# Adafruit_TCS34725.net
KiCad netlist of a schematic drawn in Altium Designer
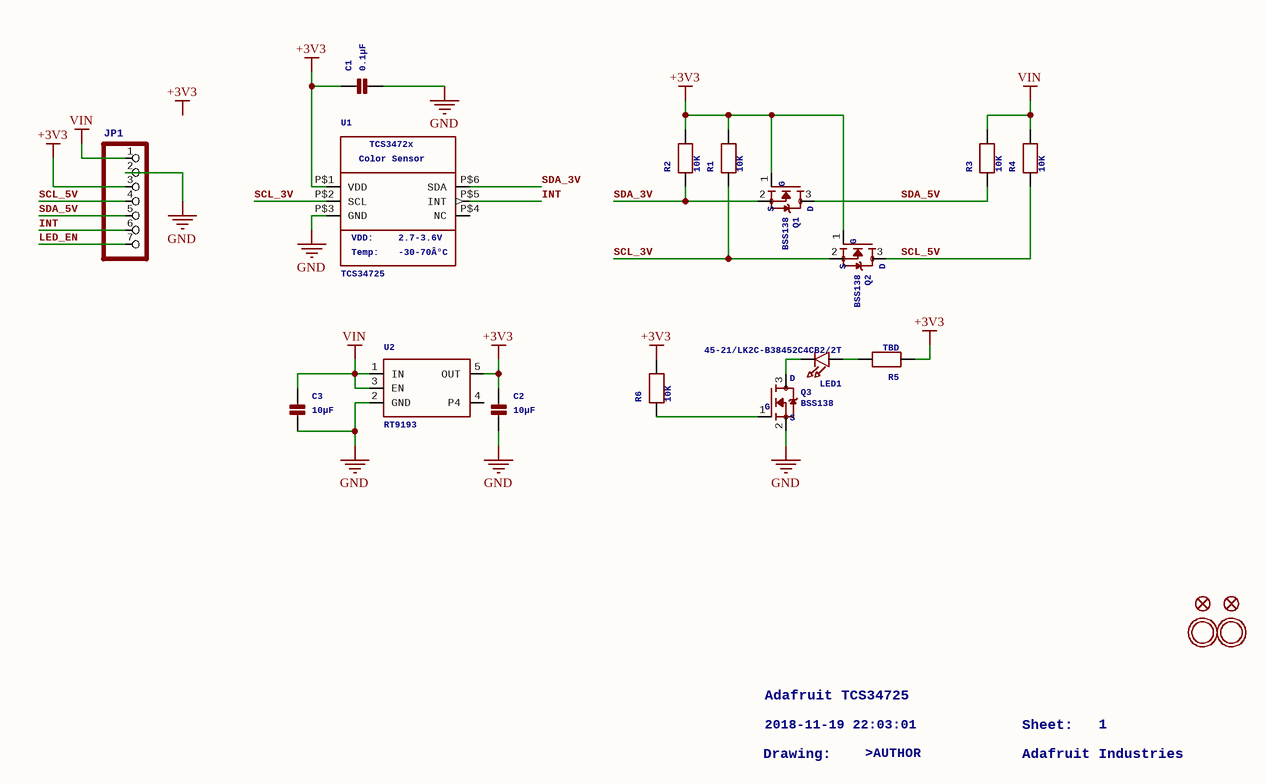
[diagram p0: Adafruit TCS34725.SchDoc]

(export (version "E")
  (design (tool "Eeschema 10.0.6"))
  (components
    (comp (ref "C1") (value "0.1µF") (footprint "_0805") (libsource (lib "") (part "CAP_CERAMIC_0805_1")))
    (comp (ref "C2")
      (value "10µF")
      (footprint "_0805")
      (libsource (lib "microbuilder") (part "CAP_CERAMIC_0805"))
    )
    (comp (ref "C3")
      (value "10µF")
      (footprint "_0805")
      (libsource (lib "microbuilder") (part "CAP_CERAMIC_0805"))
    )
    (comp (ref "FID1")
      (value "FIDUCIAL\"\"")
      (footprint "FIDUCIAL_1MM")
      (description "Fiducial Alignment PointsVarious fiducial points for machine vision alignment.")
      (libsource (lib "microbuilder") (part "FIDUCIAL{dblquote}{dblquote}"))
    )
    (comp (ref "FID2")
      (value "FIDUCIAL\"\"")
      (footprint "FIDUCIAL_1MM")
      (description "Fiducial Alignment PointsVarious fiducial points for machine vision alignment.")
      (libsource (lib "microbuilder") (part "FIDUCIAL{dblquote}{dblquote}"))
    )
    (comp (ref "JP1")
      (value "HEADER-1X770MIL")
      (footprint "1X07_ROUND_70")
      (description "PIN HEADER")
      (libsource (lib "microbuilder") (part "HEADER-1X770MIL"))
    )
    (comp (ref "LED1")
      (value "45-21/LK2C-B38452C4CB2/2T")
      (footprint "EVERLIGHT_45-21")
      (libsource (lib "microbuilder") (part "LEDEV45-21"))
    )
    (comp (ref "Q1")
      (value "BSS138")
      (footprint "SOT23-WIDE")
      (fields (field (name "D") "D") (field (name "S") "S") (field (name "G") "G"))
      (libsource (lib "microbuilder") (part "MOSFET-NWIDE"))
    )
    (comp (ref "Q2")
      (value "BSS138")
      (footprint "SOT23-WIDE")
      (fields (field (name "D") "D") (field (name "S") "S") (field (name "G") "G"))
      (libsource (lib "microbuilder") (part "MOSFET-NWIDE"))
    )
    (comp (ref "Q3")
      (value "BSS138")
      (footprint "SOT23-WIDE")
      (fields (field (name "D") "D") (field (name "S") "S") (field (name "G") "G"))
      (libsource (lib "microbuilder") (part "MOSFET-NWIDE"))
    )
    (comp (ref "R1")
      (value "10K")
      (footprint "_0805")
      (libsource (lib "microbuilder") (part "RESISTOR_0805"))
    )
    (comp (ref "R2")
      (value "10K")
      (footprint "_0805")
      (libsource (lib "microbuilder") (part "RESISTOR_0805"))
    )
    (comp (ref "R3")
      (value "10K")
      (footprint "_0805")
      (libsource (lib "microbuilder") (part "RESISTOR_0805"))
    )
    (comp (ref "R4")
      (value "10K")
      (footprint "_0805")
      (libsource (lib "microbuilder") (part "RESISTOR_0805"))
    )
    (comp (ref "R5")
      (value "TBD")
      (footprint "_0805")
      (libsource (lib "microbuilder") (part "RESISTOR_0805"))
    )
    (comp (ref "R6")
      (value "10K")
      (footprint "_0805")
      (libsource (lib "microbuilder") (part "RESISTOR_0805"))
    )
    (comp (ref "U$8")
      (value "MOUNTINGHOLE2.5")
      (footprint "MOUNTINGHOLE_2.5_PLATED")
      (description "Mounting HoleFor #2 screws (0.086\"/2.18mm width, 0.094\"/2.4mm hole) use 2.5mm")
      (libsource (lib "microbuilder") (part "MOUNTINGHOLE2.5"))
    )
    (comp (ref "U$14")
      (value "MOUNTINGHOLE2.5")
      (footprint "MOUNTINGHOLE_2.5_PLATED")
      (description "Mounting HoleFor #2 screws (0.086\"/2.18mm width, 0.094\"/2.4mm hole) use 2.5mm")
      (libsource (lib "microbuilder") (part "MOUNTINGHOLE2.5"))
    )
    (comp (ref "U1")
      (value "TCS34725")
      (footprint "TCS3472_FN6")
      (description "TCS3472 RGB + Clear Color SensorPart IDs")
      (fields
        (field (name "TCS3472X") "TCS3472x")
        (field (name "COLORSENSOR") "Color Sensor")
        (field (name "VDD") "VDD:")
        (field (name "TEMP") "Temp:")
        (field (name "2.7-3.6V") "2.7-3.6V")
        (field (name "-30-70掳C") "-30-70掳C")
      )
      (libsource (lib "microbuilder") (part "LIGHT_TCS3472"))
    )
    (comp (ref "U2")
      (value "RT9193")
      (footprint "SOT23-5")
      (libsource (lib "microbuilder") (part "VREG_SOT23-5"))
    )
  )
  (nets
    (net (code "1") (name "+3V3") (class "Default")
      (node (ref "C1") (pin "1") (pinfunction "P$1_1") (pintype "passive"))
      (node (ref "C2") (pin "1") (pinfunction "P$1_1") (pintype "passive"))
      (node (ref "JP1") (pin "3") (pinfunction "3_3") (pintype "passive"))
      (node (ref "Q1") (pin "1") (pinfunction "G_1") (pintype "passive"))
      (node (ref "Q2") (pin "1") (pinfunction "G_1") (pintype "passive"))
      (node (ref "R1") (pin "2") (pinfunction "2_2") (pintype "passive"))
      (node (ref "R2") (pin "2") (pinfunction "2_2") (pintype "passive"))
      (node (ref "R5") (pin "1") (pinfunction "1_1") (pintype "passive"))
      (node (ref "R6") (pin "2") (pinfunction "2_2") (pintype "passive"))
      (node (ref "U1") (pin "P$1") (pinfunction "VDD_P$1") (pintype "power_in"))
      (node (ref "U2") (pin "5") (pinfunction "OUT_5") (pintype "passive"))
    )
    (net (code "2") (name "/INT") (class "Default")
      (node (ref "JP1") (pin "6") (pinfunction "6_6") (pintype "passive"))
      (node (ref "U1") (pin "P$5") (pinfunction "INT_P$5") (pintype "output"))
    )
    (net (code "3") (name "/LED_EN") (class "Default")
      (node (ref "JP1") (pin "7") (pinfunction "7_7") (pintype "passive"))
    )
    (net (code "4") (name "/SCL_3V") (class "Default")
      (node (ref "Q2") (pin "2") (pinfunction "S_2") (pintype "passive"))
      (node (ref "R1") (pin "1") (pinfunction "1_1") (pintype "passive"))
      (node (ref "U1") (pin "P$2") (pinfunction "SCL_P$2") (pintype "passive"))
    )
    (net (code "5") (name "/SCL_5V") (class "Default")
      (node (ref "JP1") (pin "4") (pinfunction "4_4") (pintype "passive"))
      (node (ref "Q2") (pin "3") (pinfunction "D_3") (pintype "passive"))
      (node (ref "R4") (pin "1") (pinfunction "1_1") (pintype "passive"))
    )
    (net (code "6") (name "/SDA_3V") (class "Default")
      (node (ref "Q1") (pin "2") (pinfunction "S_2") (pintype "passive"))
      (node (ref "R2") (pin "1") (pinfunction "1_1") (pintype "passive"))
      (node (ref "U1") (pin "P$6") (pinfunction "SDA_P$6") (pintype "passive"))
    )
    (net (code "7") (name "/SDA_5V") (class "Default")
      (node (ref "JP1") (pin "5") (pinfunction "5_5") (pintype "passive"))
      (node (ref "Q1") (pin "3") (pinfunction "D_3") (pintype "passive"))
      (node (ref "R3") (pin "1") (pinfunction "1_1") (pintype "passive"))
    )
    (net (code "8") (name "GND") (class "Default")
      (node (ref "C1") (pin "2") (pinfunction "P$2_2") (pintype "passive"))
      (node (ref "C2") (pin "2") (pinfunction "P$2_2") (pintype "passive"))
      (node (ref "C3") (pin "2") (pinfunction "P$2_2") (pintype "passive"))
      (node (ref "JP1") (pin "2") (pinfunction "2_2") (pintype "passive"))
      (node (ref "Q3") (pin "2") (pinfunction "S_2") (pintype "passive"))
      (node (ref "U1") (pin "P$3") (pinfunction "GND_P$3") (pintype "power_in"))
      (node (ref "U2") (pin "2") (pinfunction "GND_2") (pintype "passive"))
    )
    (net (code "9") (name "Net-(LED1-C)") (class "Default")
      (node (ref "LED1") (pin "K") (pinfunction "C_K") (pintype "passive"))
      (node (ref "Q3") (pin "3") (pinfunction "D_3") (pintype "passive"))
    )
    (net (code "10") (name "Net-(LED1-PadA)") (class "Default")
      (node (ref "LED1") (pin "A") (pinfunction "A_A") (pintype "passive"))
      (node (ref "R5") (pin "2") (pinfunction "2_2") (pintype "passive"))
    )
    (net (code "11") (name "Net-(Q3-G)") (class "Default")
      (node (ref "Q3") (pin "1") (pinfunction "G_1") (pintype "passive"))
      (node (ref "R6") (pin "1") (pinfunction "1_1") (pintype "passive"))
    )
    (net (code "12") (name "VIN") (class "Default")
      (node (ref "C3") (pin "1") (pinfunction "P$1_1") (pintype "passive"))
      (node (ref "JP1") (pin "1") (pinfunction "1_1") (pintype "passive"))
      (node (ref "R3") (pin "2") (pinfunction "2_2") (pintype "passive"))
      (node (ref "R4") (pin "2") (pinfunction "2_2") (pintype "passive"))
      (node (ref "U2") (pin "1") (pinfunction "IN_1") (pintype "passive"))
      (node (ref "U2") (pin "3") (pinfunction "EN_3") (pintype "passive"))
    )
    (net (code "13") (name "unconnected-(U1-NC-PadP$4)") (class "Default")
      (node (ref "U1") (pin "P$4") (pinfunction "NC_P$4") (pintype "passive"))
    )
    (net (code "14") (name "unconnected-(U2-P4-Pad4)") (class "Default")
      (node (ref "U2") (pin "4") (pinfunction "P4_4") (pintype "passive"))
    )
  )
)
